# Industrial_Radio.net
KiCad netlist of a schematic drawn in Altium Designer
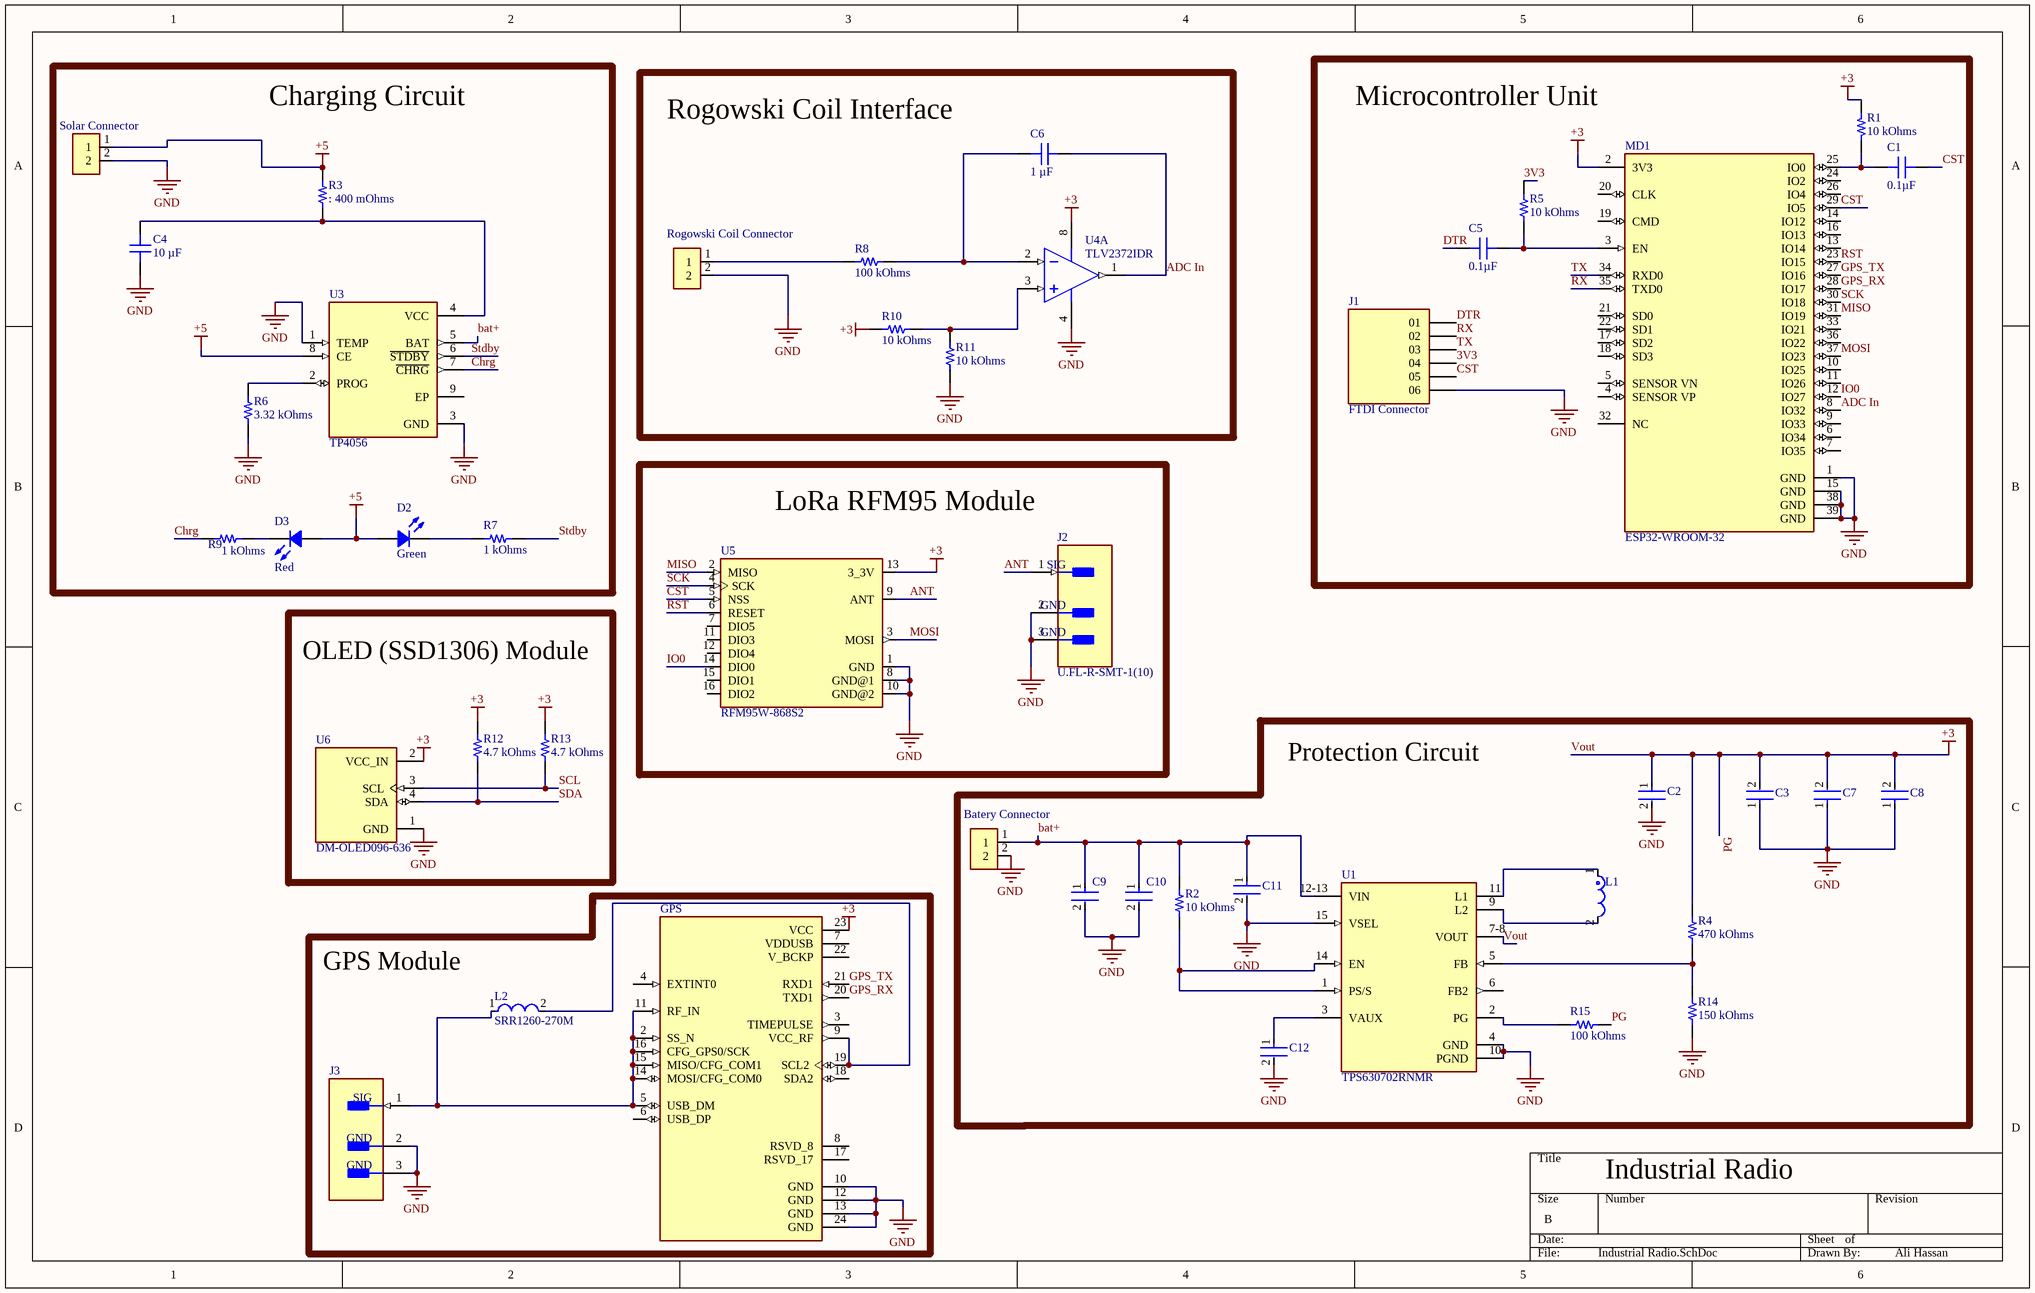
[diagram p0: Industrial Radio.SchDoc]

(export (version "E")
  (design (tool "Eeschema 10.0.6"))
  (components
    (comp (ref "Batery Connector")
      (value "B2B-PH-SM4-TB(LF)(SN)")
      (footprint "B2B-PH-SM4-TB(LF)(SN)")
      (description "Connector Header Surface Mount 2 position 0.079 (2.00mm)")
      (fields (field (name "MF") "JST Sales"))
      (libsource (lib "B2B-PH-SM4-TB_LF__SN_") (part "B2B-PH-SM4-TB(LF)(SN)"))
    )
    (comp (ref "C1")
      (value "0.1µF")
      (footprint "CAP 0603_1608")
      (description "CAP CER 0.1UF 25V X7R 0603")
      (fields
        (field (name "PART NUMBER") "06033C104K4T4A")
        (field (name "CAPACITANCE") "0.1µF")
        (field (name "MANUFACTURER") "AVX Corporation")
      )
      (libsource (lib "Celestial Altium Library - altium_library") (part "Capacitor"))
    )
    (comp (ref "C2")
      (value "TMK107BBJ106MA-T")
      (footprint "FP-0603-L_1_6_0_2-W_0_8_0-MFG")
      (description "Multilayer Ceramic Capacitor 10uF 25V X5R 20% SMD 0603 T/R")
      (fields (field (name "TOLERANCE") "20%"))
      (libsource (lib "Altium Content Vault") (part "b4654b650e69147ec39a6b967a45e02"))
    )
    (comp (ref "C3")
      (value "GRM21BC81C226ME44L")
      (footprint "FP-GRM21B-0_2-e0_2_0_7-MFG")
      (description "Chip Multilayer Ceramic Capacitors for General Purpose, 0805, 22uF, X6S, 22%, 20%, 16V")
      (fields (field (name "TOLERANCE") "20%"))
      (libsource (lib "Altium Content Vault") (part "b4654b650e69147ec39a6b967a45e02"))
    )
    (comp (ref "C4")
      (value "10 µF")
      (footprint "MURATA GRM188 0603_1608")
      (description "CAP CER 10UF 2.5V X6S 0603")
      (fields
        (field (name "PART NUMBER") "GRM188C80E106ME47D")
        (field (name "CAPACITANCE") "10 µF")
        (field (name "MANUFACTURER") "Murata Electronics")
      )
      (libsource (lib "Celestial Altium Library - altium_library") (part "Capacitor"))
    )
    (comp (ref "C5")
      (value "0.1µF")
      (footprint "CAP 0603_1608")
      (description "CAP CER 0.1UF 25V X7R 0603")
      (fields
        (field (name "PART NUMBER") "06033C104K4T4A")
        (field (name "CAPACITANCE") "0.1µF")
        (field (name "MANUFACTURER") "AVX Corporation")
      )
      (libsource (lib "Celestial Altium Library - altium_library") (part "Capacitor"))
    )
    (comp (ref "C6")
      (value "1 µF")
      (footprint "CAP 0603_1608")
      (description "CAP CER 1UF 6.3V X7R 0603")
      (fields
        (field (name "PART NUMBER") "C0603X105M9RACAUTO")
        (field (name "CAPACITANCE") "1 µF")
        (field (name "MANUFACTURER") "KEMET")
      )
      (libsource (lib "Celestial Altium Library - altium_library") (part "Capacitor"))
    )
    (comp (ref "C7")
      (value "GRM21BC81C226ME44L")
      (footprint "FP-GRM21B-0_2-e0_2_0_7-MFG")
      (description "Chip Multilayer Ceramic Capacitors for General Purpose, 0805, 22uF, X6S, 22%, 20%, 16V")
      (fields (field (name "TOLERANCE") "20%"))
      (libsource (lib "Altium Content Vault") (part "b4654b650e69147ec39a6b967a45e02"))
    )
    (comp (ref "C8")
      (value "GRM21BC81C226ME44L")
      (footprint "FP-GRM21B-0_2-e0_2_0_7-MFG")
      (description "Chip Multilayer Ceramic Capacitors for General Purpose, 0805, 22uF, X6S, 22%, 20%, 16V")
      (fields (field (name "TOLERANCE") "20%"))
      (libsource (lib "Altium Content Vault") (part "b4654b650e69147ec39a6b967a45e02"))
    )
    (comp (ref "C9")
      (value "GRM21BC71E106ME11L")
      (footprint "FP-GRM21B-0_2-e0_2_0_7-IPC_A")
      (description "Chip Multilayer Ceramic Capacitors for General Purpose, 0805, 10uF, X7S, 22%, 20%, 25V")
      (fields (field (name "TOLERANCE") "20%"))
      (libsource (lib "Altium Content Vault") (part "b4654b650e69147ec39a6b967a45e02"))
    )
    (comp (ref "C10")
      (value "GRM21BC71E106ME11L")
      (footprint "FP-GRM21B-0_2-e0_2_0_7-IPC_A")
      (description "Chip Multilayer Ceramic Capacitors for General Purpose, 0805, 10uF, X7S, 22%, 20%, 25V")
      (fields (field (name "TOLERANCE") "20%"))
      (libsource (lib "Altium Content Vault") (part "b4654b650e69147ec39a6b967a45e02"))
    )
    (comp (ref "C11")
      (value "TMK107BBJ106MA-T")
      (footprint "FP-0603-L_1_6_0_2-W_0_8_0-MFG")
      (description "Multilayer Ceramic Capacitor 10uF 25V X5R 20% SMD 0603 T/R")
      (fields (field (name "TOLERANCE") "20%"))
      (libsource (lib "Altium Content Vault") (part "b4654b650e69147ec39a6b967a45e02"))
    )
    (comp (ref "C12")
      (value "TMK105B7104MV-FR")
      (footprint "FP-0402-L_1_0_0_05-W_0_5-IPC_B")
      (description "None")
      (fields (field (name "TOLERANCE") "20%"))
      (libsource (lib "Altium Content Vault") (part "b4654b650e69147ec39a6b967a45e02"))
    )
    (comp (ref "D2")
      (value "Green")
      (footprint "LED 1206_3216 GREEN")
      (description "LED GREEN SMD")
      (fields (field (name "PART NUMBER") "HSMQ-C380") (field (name "MANUFACTURER") "Broadcom Limited"))
      (libsource (lib "Celestial Altium Library - altium_library") (part "LED"))
    )
    (comp (ref "D3")
      (value "Red")
      (footprint "LED 1206_3216 RED")
      (description "LED RED SMD")
      (fields (field (name "PART NUMBER") "HSMC-C380") (field (name "MANUFACTURER") "Broadcom Limited"))
      (libsource (lib "Celestial Altium Library - altium_library") (part "LED"))
    )
    (comp (ref "GPS")
      (value "NEO-6M-GPS")
      (footprint "XCVR_NEO-6M-GPS")
      (description "GPS Development Tools SparkFun GNSS-RTK Dead Reckoning Breakout - ZED-F9K (Qwiic)")
      (fields (field (name "MF") "u-blox"))
      (libsource (lib "NEO-6M-GPS") (part "NEO-6M-GPS"))
    )
    (comp (ref "J1")
      (value "FTDI Connector")
      (footprint "SAMTEC_MTSW-106-09-G-S-375-RA")
      (description "Connector Header Through Hole, Right Angle 6 position 0.100 (2.54mm)")
      (fields (field (name "MF") "Samtec Inc.") (field (name "MP") "MTSW-106-09-G-S-375-RA"))
      (libsource (lib "MTSW-106-09-G-S-375-RA") (part "MTSW-106-09-G-S-375-RA"))
    )
    (comp (ref "J2")
      (value "U.FL-R-SMT-1(10)")
      (footprint "FP-U_FL-R-SMT-1_10-MFG")
      (description "CONN U.FL RCPT STR 50 OHM SMD")
      (libsource (lib "Altium Content Vault") (part "7158abf7d987fa84906f6fb0d115710"))
    )
    (comp (ref "J3")
      (value "U.FL-R-SMT-1(10)")
      (footprint "FP-U_FL-R-SMT-1_10-MFG")
      (description "CONN U.FL RCPT STR 50 OHM SMD")
      (libsource (lib "") (part "7158abf7d987fa84906f6fb0d115710_1"))
    )
    (comp (ref "L1")
      (value "XFL4020-152MEC")
      (footprint "FP-XFL4020-MFG")
      (fields (field (name "TOLERANCE") "20%"))
      (libsource (lib "Altium Content Vault") (part "4cc4b267dca4c8e51f7102f422741d8"))
    )
    (comp (ref "L2")
      (value "SRR1260-270M")
      (footprint "FP-SRR1260-MFG")
      (description "FIXED IND 27UH 3.6A 45 MOHM SMD")
      (fields (field (name "TOLERANCE") "20%") (field (name "MANUFACTURER") "Bourns"))
      (libsource (lib "Altium Content Vault") (part "725321dda6339637d4d059423bc1c3c"))
    )
    (comp (ref "MD1")
      (value "ESP32-WROOM-32")
      (footprint "FP-ESP32-WROOM-32-MFG")
      (description "RX TXRX MOD WIFI SURFACE MOUNT")
      (libsource (lib "Altium Content Vault") (part "ee866abf0b6c51247b7f5cdebf2f250"))
    )
    (comp (ref "R1")
      (value "10 kOhms")
      (footprint "RES 0603_1608")
      (description "RES SMD 10K OHM 5% 1/10W 0603")
      (fields (field (name "PART NUMBER") "CRCW060310K0JNEA") (field (name "MANUFACTURER") "Vishay Dale"))
      (libsource (lib "Celestial Altium Library - altium_library") (part "Resistor"))
    )
    (comp (ref "R2")
      (value "10 kOhms")
      (footprint "RES 0603_1608")
      (description "RES 10K OHM 0.1% 1/16W 0603")
      (fields
        (field (name "PART NUMBER") "RNCS0603BKE10K0")
        (field (name "MANUFACTURER") "Stackpole Electronics Inc")
      )
      (libsource (lib "Celestial Altium Library - altium_library") (part "Resistor"))
    )
    (comp (ref "R3")
      (value "~")
      (footprint "YAGEO RES 0603_1608")
      (description "RES 0.4 OHM 1% 1/10W 0603")
      (fields
        (field (name "PART NUMBER") "RL0603FR-070R4L")
        (field (name "ALTIUM_UNNAMED_1") "400 mOhms")
        (field (name "MANUFACTURER") "Yageo")
      )
      (libsource (lib "Celestial Altium Library - altium_library") (part "Resistor"))
    )
    (comp (ref "R4")
      (value "470 kOhms")
      (footprint "YAGEO RES 0603_1608")
      (description "RES SMD 470K OHM 5% 1/10W 0603")
      (fields (field (name "PART NUMBER") "AC0603JR-07470KL") (field (name "MANUFACTURER") "Yageo"))
      (libsource (lib "Celestial Altium Library - altium_library") (part "Resistor"))
    )
    (comp (ref "R5")
      (value "10 kOhms")
      (footprint "RES 0603_1608")
      (description "RES SMD 10K OHM 5% 1/10W 0603")
      (fields (field (name "PART NUMBER") "CRCW060310K0JNEA") (field (name "MANUFACTURER") "Vishay Dale"))
      (libsource (lib "Celestial Altium Library - altium_library") (part "Resistor"))
    )
    (comp (ref "R6")
      (value "3.32 kOhms")
      (footprint "RES 0603_1608")
      (description "RES SMD 3.32K OHM 0.1% 1/5W 0603")
      (fields
        (field (name "PART NUMBER") "ERJ-PB3B3321V")
        (field (name "MANUFACTURER") "Panasonic Electronic Components")
      )
      (libsource (lib "Celestial Altium Library - altium_library") (part "Resistor"))
    )
    (comp (ref "R7")
      (value "1 kOhms")
      (footprint "RES 0603_1608")
      (description "RES SMD 1K OHM 0.1% 1/16W 0603")
      (fields
        (field (name "PART NUMBER") "CPF0603B1K0E")
        (field (name "MANUFACTURER") "TE Connectivity Passive Product")
      )
      (libsource (lib "Celestial Altium Library - altium_library") (part "Resistor"))
    )
    (comp (ref "R8")
      (value "100 kOhms")
      (footprint "RES 0603_1608")
      (description "RES 100K OHM 0.1% 1/16W 0603")
      (fields
        (field (name "PART NUMBER") "RNCS0603BKE100K")
        (field (name "MANUFACTURER") "Stackpole Electronics Inc")
      )
      (libsource (lib "Celestial Altium Library - altium_library") (part "Resistor"))
    )
    (comp (ref "R9")
      (value "1 kOhms")
      (footprint "RES 0603_1608")
      (description "RES SMD 1K OHM 0.1% 1/16W 0603")
      (fields
        (field (name "PART NUMBER") "CPF0603B1K0E")
        (field (name "MANUFACTURER") "TE Connectivity Passive Product")
      )
      (libsource (lib "Celestial Altium Library - altium_library") (part "Resistor"))
    )
    (comp (ref "R10")
      (value "10 kOhms")
      (footprint "RES 0603_1608")
      (description "RES SMD 10K OHM 5% 1/10W 0603")
      (fields (field (name "PART NUMBER") "CRCW060310K0JNEA") (field (name "MANUFACTURER") "Vishay Dale"))
      (libsource (lib "Celestial Altium Library - altium_library") (part "Resistor"))
    )
    (comp (ref "R11")
      (value "10 kOhms")
      (footprint "RES 0603_1608")
      (description "RES SMD 10K OHM 5% 1/10W 0603")
      (fields (field (name "PART NUMBER") "CRCW060310K0JNEA") (field (name "MANUFACTURER") "Vishay Dale"))
      (libsource (lib "Celestial Altium Library - altium_library") (part "Resistor"))
    )
    (comp (ref "R12")
      (value "4.7 kOhms")
      (footprint "RES 0603_1608")
      (description "RES SMD 4.7K OHM 0.1% 1/10W 0603")
      (fields
        (field (name "PART NUMBER") "ERA-3AEB472V")
        (field (name "MANUFACTURER") "Panasonic Electronic Components")
      )
      (libsource (lib "Celestial Altium Library - altium_library") (part "Resistor"))
    )
    (comp (ref "R13")
      (value "4.7 kOhms")
      (footprint "RES 0603_1608")
      (description "RES SMD 4.7K OHM 0.1% 1/10W 0603")
      (fields
        (field (name "PART NUMBER") "ERA-3AEB472V")
        (field (name "MANUFACTURER") "Panasonic Electronic Components")
      )
      (libsource (lib "Celestial Altium Library - altium_library") (part "Resistor"))
    )
    (comp (ref "R14")
      (value "150 kOhms")
      (footprint "RES 0603_1608")
      (description "RES 150K OHM 1% 1/4W 0603")
      (fields
        (field (name "PART NUMBER") "CRGP0603F150K")
        (field (name "MANUFACTURER") "TE Connectivity Passive Product")
      )
      (libsource (lib "Celestial Altium Library - altium_library") (part "Resistor"))
    )
    (comp (ref "R15")
      (value "100 kOhms")
      (footprint "RES 0603_1608")
      (description "RES 100K OHM 0.1% 1/16W 0603")
      (fields
        (field (name "PART NUMBER") "RNCS0603BKE100K")
        (field (name "MANUFACTURER") "Stackpole Electronics Inc")
      )
      (libsource (lib "Celestial Altium Library - altium_library") (part "Resistor"))
    )
    (comp (ref "Rogowski Coil Connector")
      (value "B2B-PH-SM4-TB(LF)(SN)")
      (footprint "B2B-PH-SM4-TB(LF)(SN)")
      (description "Connector Header Surface Mount 2 position 0.079 (2.00mm)")
      (fields (field (name "MF") "JST Sales"))
      (libsource (lib "B2B-PH-SM4-TB_LF__SN_") (part "B2B-PH-SM4-TB(LF)(SN)"))
    )
    (comp (ref "Solar Connector")
      (value "B2B-PH-SM4-TB(LF)(SN)")
      (footprint "B2B-PH-SM4-TB(LF)(SN)")
      (description "Connector Header Surface Mount 2 position 0.079 (2.00mm)")
      (fields (field (name "MF") "JST Sales"))
      (libsource (lib "B2B-PH-SM4-TB_LF__SN_") (part "B2B-PH-SM4-TB(LF)(SN)"))
    )
    (comp (ref "U1")
      (value "TPS630702RNMR")
      (footprint "FP-RNM0015A-MFG")
      (description "POWER MANAGEMENT")
      (libsource (lib "Altium Content Vault") (part "3b4d2662cd6691273d8b1fe1e725472"))
    )
    (comp (ref "U3")
      (value "TP4056")
      (footprint "SOP127P600X175-9N")
      (description "Complete single cell Li-Ion battery with a constant current / constant voltage linear charger")
      (fields (field (name "MF") "NanJing Top Power ASIC Corp."))
      (libsource (lib "TP4056") (part "TP4056"))
    )
    (comp (ref "U4")
      (value "TLV2372IDR")
      (footprint "D0008A_M")
      (fields (field (name "MANUFACTURER") "Texas Instruments"))
      (libsource (lib "Altium Content Vault") (part "TI-TLV_TLC-8"))
    )
    (comp (ref "U5")
      (value "RFM95W-868S2")
      (footprint "XCVR_RFM95W-868S2")
      (description "General ISM < 1GHz LoRaâ„¢ Transceiver Module 868MHz Antenna Not Included Surface Mount")
      (fields (field (name "MF") "RF"))
      (libsource (lib "RFM95W-868S2") (part "RFM95W-868S2"))
    )
    (comp (ref "U6")
      (value "DM-OLED096-636")
      (footprint "MODULE_DM-OLED096-636")
      (description "0.96â€ 128 X 64 MONOCHROME GRAPHIC OLED DISPLAY MODULE - I2C")
      (fields (field (name "MF") "Display Module"))
      (libsource (lib "DM-OLED096-636") (part "DM-OLED096-636"))
    )
  )
  (nets
    (net (code "1") (name "+3") (class "Default")
      (node (ref "C2") (pin "1") (pinfunction "1_1") (pintype "passive"))
      (node (ref "C3") (pin "2") (pinfunction "2_2") (pintype "passive"))
      (node (ref "C7") (pin "2") (pinfunction "2_2") (pintype "passive"))
      (node (ref "C8") (pin "2") (pinfunction "2_2") (pintype "passive"))
      (node (ref "GPS") (pin "23") (pinfunction "VCC_23") (pintype "power_in"))
      (node (ref "MD1") (pin "2") (pinfunction "3V3_2") (pintype "power_in"))
      (node (ref "R1") (pin "2") (pinfunction "2_2") (pintype "passive"))
      (node (ref "R10") (pin "1") (pinfunction "1_1") (pintype "passive"))
      (node (ref "R12") (pin "1") (pinfunction "1_1") (pintype "passive"))
      (node (ref "R13") (pin "1") (pinfunction "1_1") (pintype "passive"))
      (node (ref "R15") (pin "1") (pinfunction "1_1") (pintype "passive"))
      (node (ref "R4") (pin "2") (pinfunction "2_2") (pintype "passive"))
      (node (ref "U1") (pin "7-8") (pinfunction "VOUT_7-8") (pintype "passive"))
      (node (ref "U4") (pin "8") (pinfunction "VDD_8") (pintype "power_in"))
      (node (ref "U5") (pin "13") (pinfunction "3_3V_13") (pintype "power_in"))
      (node (ref "U6") (pin "2") (pinfunction "VCC_IN_2") (pintype "power_in"))
    )
    (net (code "2") (name "+5") (class "Default")
      (node (ref "D2") (pin "1") (pinfunction "1_1") (pintype "passive"))
      (node (ref "D3") (pin "1") (pinfunction "1_1") (pintype "passive"))
      (node (ref "R3") (pin "2") (pinfunction "2_2") (pintype "passive"))
      (node (ref "Solar Connector") (pin "1") (pinfunction "1_1") (pintype "bidirectional"))
      (node (ref "U3") (pin "8") (pinfunction "CE_8") (pintype "input"))
    )
    (net (code "3") (name "/3V3") (class "Default")
      (node (ref "J1") (pin "04") (pinfunction "04_04") (pintype "passive"))
      (node (ref "R5") (pin "2") (pinfunction "2_2") (pintype "passive"))
    )
    (net (code "4") (name "/ADC In") (class "Default")
      (node (ref "C6") (pin "2") (pinfunction "2_2") (pintype "passive"))
      (node (ref "MD1") (pin "8") (pinfunction "IO32_8") (pintype "bidirectional"))
      (node (ref "U4") (pin "1") (pinfunction "OUT1_1") (pintype "output"))
    )
    (net (code "5") (name "/ANT") (class "Default")
      (node (ref "J2") (pin "1") (pinfunction "SIG_1") (pintype "input"))
      (node (ref "U5") (pin "9") (pinfunction "ANT_9") (pintype "passive"))
    )
    (net (code "6") (name "/CST") (class "Default")
      (node (ref "C1") (pin "1") (pinfunction "1_1") (pintype "passive"))
      (node (ref "J1") (pin "05") (pinfunction "05_05") (pintype "passive"))
      (node (ref "MD1") (pin "29") (pinfunction "IO5_29") (pintype "bidirectional"))
      (node (ref "U5") (pin "5") (pinfunction "NSS_5") (pintype "input"))
    )
    (net (code "7") (name "/Chrg") (class "Default")
      (node (ref "R9") (pin "1") (pinfunction "1_1") (pintype "passive"))
      (node (ref "U3") (pin "7") (pinfunction "~{CHRG}_7") (pintype "output"))
    )
    (net (code "8") (name "/DTR") (class "Default")
      (node (ref "C5") (pin "1") (pinfunction "1_1") (pintype "passive"))
      (node (ref "J1") (pin "01") (pinfunction "01_01") (pintype "passive"))
    )
    (net (code "9") (name "/GPS_RX") (class "Default")
      (node (ref "GPS") (pin "20") (pinfunction "TXD1_20") (pintype "output"))
      (node (ref "MD1") (pin "28") (pinfunction "IO17_28") (pintype "bidirectional"))
    )
    (net (code "10") (name "/GPS_TX") (class "Default")
      (node (ref "GPS") (pin "21") (pinfunction "RXD1_21") (pintype "input"))
      (node (ref "MD1") (pin "27") (pinfunction "IO16_27") (pintype "bidirectional"))
    )
    (net (code "11") (name "/IO0") (class "Default")
      (node (ref "MD1") (pin "12") (pinfunction "IO27_12") (pintype "bidirectional"))
      (node (ref "U5") (pin "14") (pinfunction "DIO0_14") (pintype "bidirectional"))
    )
    (net (code "12") (name "/MISO") (class "Default")
      (node (ref "MD1") (pin "31") (pinfunction "IO19_31") (pintype "bidirectional"))
      (node (ref "U5") (pin "2") (pinfunction "MISO_2") (pintype "input"))
    )
    (net (code "13") (name "/MOSI") (class "Default")
      (node (ref "MD1") (pin "37") (pinfunction "IO23_37") (pintype "bidirectional"))
      (node (ref "U5") (pin "3") (pinfunction "MOSI_3") (pintype "output"))
    )
    (net (code "14") (name "/RST") (class "Default")
      (node (ref "MD1") (pin "23") (pinfunction "IO15_23") (pintype "bidirectional"))
      (node (ref "U5") (pin "6") (pinfunction "RESET_6") (pintype "bidirectional"))
    )
    (net (code "15") (name "/RX") (class "Default")
      (node (ref "J1") (pin "02") (pinfunction "02_02") (pintype "passive"))
      (node (ref "MD1") (pin "35") (pinfunction "TXD0_35") (pintype "bidirectional"))
    )
    (net (code "16") (name "/SCK") (class "Default")
      (node (ref "MD1") (pin "30") (pinfunction "IO18_30") (pintype "bidirectional"))
      (node (ref "U5") (pin "4") (pinfunction "SCK_4") (pintype "input"))
    )
    (net (code "17") (name "/SCL") (class "Default")
      (node (ref "R13") (pin "2") (pinfunction "2_2") (pintype "passive"))
      (node (ref "U6") (pin "3") (pinfunction "SCL_3") (pintype "input"))
    )
    (net (code "18") (name "/SDA") (class "Default")
      (node (ref "R12") (pin "2") (pinfunction "2_2") (pintype "passive"))
      (node (ref "U6") (pin "4") (pinfunction "SDA_4") (pintype "bidirectional"))
    )
    (net (code "19") (name "/Stdby") (class "Default")
      (node (ref "R7") (pin "1") (pinfunction "1_1") (pintype "passive"))
      (node (ref "U3") (pin "6") (pinfunction "~{STDBY}_6") (pintype "output"))
    )
    (net (code "20") (name "/TX") (class "Default")
      (node (ref "J1") (pin "03") (pinfunction "03_03") (pintype "passive"))
      (node (ref "MD1") (pin "34") (pinfunction "RXD0_34") (pintype "bidirectional"))
    )
    (net (code "21") (name "/bat+") (class "Default")
      (node (ref "Batery Connector") (pin "1") (pinfunction "1_1") (pintype "bidirectional"))
      (node (ref "C10") (pin "1") (pinfunction "1_1") (pintype "passive"))
      (node (ref "C11") (pin "1") (pinfunction "1_1") (pintype "passive"))
      (node (ref "C9") (pin "1") (pinfunction "1_1") (pintype "passive"))
      (node (ref "R2") (pin "2") (pinfunction "2_2") (pintype "passive"))
      (node (ref "U1") (pin "12-13") (pinfunction "VIN_12-13") (pintype "power_in"))
      (node (ref "U3") (pin "5") (pinfunction "BAT_5") (pintype "output"))
    )
    (net (code "22") (name "GND") (class "Default")
      (node (ref "Batery Connector") (pin "2") (pinfunction "2_2") (pintype "bidirectional"))
      (node (ref "C10") (pin "2") (pinfunction "2_2") (pintype "passive"))
      (node (ref "C11") (pin "2") (pinfunction "2_2") (pintype "passive"))
      (node (ref "C12") (pin "2") (pinfunction "2_2") (pintype "passive"))
      (node (ref "C2") (pin "2") (pinfunction "2_2") (pintype "passive"))
      (node (ref "C3") (pin "1") (pinfunction "1_1") (pintype "passive"))
      (node (ref "C4") (pin "1") (pinfunction "1_1") (pintype "passive"))
      (node (ref "C7") (pin "1") (pinfunction "1_1") (pintype "passive"))
      (node (ref "C8") (pin "1") (pinfunction "1_1") (pintype "passive"))
      (node (ref "C9") (pin "2") (pinfunction "2_2") (pintype "passive"))
      (node (ref "GPS") (pin "10") (pinfunction "GND_10") (pintype "power_in"))
      (node (ref "GPS") (pin "12") (pinfunction "GND_12") (pintype "power_in"))
      (node (ref "GPS") (pin "13") (pinfunction "GND_13") (pintype "power_in"))
      (node (ref "GPS") (pin "24") (pinfunction "GND_24") (pintype "power_in"))
      (node (ref "J1") (pin "06") (pinfunction "06_06") (pintype "passive"))
      (node (ref "J2") (pin "2") (pinfunction "GND_2") (pintype "power_in"))
      (node (ref "J2") (pin "3") (pinfunction "GND_3") (pintype "power_in"))
      (node (ref "J3") (pin "2") (pinfunction "GND_2") (pintype "power_in"))
      (node (ref "J3") (pin "3") (pinfunction "GND_3") (pintype "power_in"))
      (node (ref "MD1") (pin "1") (pinfunction "GND_1") (pintype "power_in"))
      (node (ref "MD1") (pin "15") (pinfunction "GND_15") (pintype "power_in"))
      (node (ref "MD1") (pin "38") (pinfunction "GND_38") (pintype "power_in"))
      (node (ref "MD1") (pin "39") (pinfunction "GND_39") (pintype "power_in"))
      (node (ref "R11") (pin "1") (pinfunction "1_1") (pintype "passive"))
      (node (ref "R14") (pin "1") (pinfunction "1_1") (pintype "passive"))
      (node (ref "R6") (pin "1") (pinfunction "1_1") (pintype "passive"))
      (node (ref "Rogowski Coil Connector") (pin "2") (pinfunction "2_2") (pintype "bidirectional"))
      (node (ref "Solar Connector") (pin "2") (pinfunction "2_2") (pintype "bidirectional"))
      (node (ref "U1") (pin "10") (pinfunction "PGND_10") (pintype "power_in"))
      (node (ref "U1") (pin "15") (pinfunction "VSEL_15") (pintype "input"))
      (node (ref "U1") (pin "4") (pinfunction "GND_4") (pintype "power_in"))
      (node (ref "U3") (pin "1") (pinfunction "TEMP_1") (pintype "input"))
      (node (ref "U3") (pin "3") (pinfunction "GND_3") (pintype "power_in"))
      (node (ref "U4") (pin "4") (pinfunction "GND_4") (pintype "power_in"))
      (node (ref "U5") (pin "1") (pinfunction "GND_1") (pintype "power_in"))
      (node (ref "U5") (pin "10") (pinfunction "GND@2_10") (pintype "power_in"))
      (node (ref "U5") (pin "8") (pinfunction "GND@1_8") (pintype "power_in"))
      (node (ref "U6") (pin "1") (pinfunction "GND_1") (pintype "power_in"))
    )
    (net (code "23") (name "Net-(D2-Pad2)") (class "Default")
      (node (ref "D2") (pin "2") (pinfunction "2_2") (pintype "passive"))
      (node (ref "R7") (pin "2") (pinfunction "2_2") (pintype "passive"))
    )
    (net (code "24") (name "Net-(D3-Pad2)") (class "Default")
      (node (ref "D3") (pin "2") (pinfunction "2_2") (pintype "passive"))
      (node (ref "R9") (pin "2") (pinfunction "2_2") (pintype "passive"))
    )
    (net (code "25") (name "Net-(GPS-CFG_GPS0{slash}SCK)") (class "Default")
      (node (ref "GPS") (pin "11") (pinfunction "RF_IN_11") (pintype "input"))
      (node (ref "GPS") (pin "14") (pinfunction "MOSI/CFG_COM0_14") (pintype "bidirectional"))
      (node (ref "GPS") (pin "15") (pinfunction "MISO/CFG_COM1_15") (pintype "input"))
      (node (ref "GPS") (pin "16") (pinfunction "CFG_GPS0/SCK_16") (pintype "input"))
      (node (ref "GPS") (pin "2") (pinfunction "SS_N_2") (pintype "input"))
      (node (ref "GPS") (pin "5") (pinfunction "USB_DM_5") (pintype "bidirectional"))
      (node (ref "J3") (pin "1") (pinfunction "SIG_1") (pintype "input"))
      (node (ref "L2") (pin "1") (pinfunction "1_1") (pintype "passive"))
    )
    (net (code "26") (name "Net-(GPS-SCL2)") (class "Default")
      (node (ref "GPS") (pin "19") (pinfunction "SCL2_19") (pintype "bidirectional"))
      (node (ref "GPS") (pin "9") (pinfunction "VCC_RF_9") (pintype "output"))
      (node (ref "L2") (pin "2") (pinfunction "2_2") (pintype "passive"))
    )
    (net (code "27") (name "Net-(MD1-EN)") (class "Default")
      (node (ref "C5") (pin "2") (pinfunction "2_2") (pintype "passive"))
      (node (ref "MD1") (pin "3") (pinfunction "EN_3") (pintype "input"))
      (node (ref "R5") (pin "1") (pinfunction "1_1") (pintype "passive"))
    )
    (net (code "28") (name "Net-(MD1-IO0)") (class "Default")
      (node (ref "C1") (pin "2") (pinfunction "2_2") (pintype "passive"))
      (node (ref "MD1") (pin "25") (pinfunction "IO0_25") (pintype "bidirectional"))
      (node (ref "R1") (pin "1") (pinfunction "1_1") (pintype "passive"))
    )
    (net (code "29") (name "Net-(R8-Pad1)") (class "Default")
      (node (ref "R8") (pin "1") (pinfunction "1_1") (pintype "passive"))
      (node (ref "Rogowski Coil Connector") (pin "1") (pinfunction "1_1") (pintype "bidirectional"))
    )
    (net (code "30") (name "Net-(U1-EN)") (class "Default")
      (node (ref "R2") (pin "1") (pinfunction "1_1") (pintype "passive"))
      (node (ref "U1") (pin "1") (pinfunction "PS/S_1") (pintype "input"))
      (node (ref "U1") (pin "14") (pinfunction "EN_14") (pintype "input"))
    )
    (net (code "31") (name "Net-(U1-FB)") (class "Default")
      (node (ref "R14") (pin "2") (pinfunction "2_2") (pintype "passive"))
      (node (ref "R4") (pin "1") (pinfunction "1_1") (pintype "passive"))
      (node (ref "U1") (pin "5") (pinfunction "FB_5") (pintype "input"))
    )
    (net (code "32") (name "Net-(U1-L1)") (class "Default")
      (node (ref "L1") (pin "1") (pinfunction "1_1") (pintype "passive"))
      (node (ref "U1") (pin "11") (pinfunction "L1_11") (pintype "passive"))
    )
    (net (code "33") (name "Net-(U1-L2)") (class "Default")
      (node (ref "L1") (pin "2") (pinfunction "2_2") (pintype "passive"))
      (node (ref "U1") (pin "9") (pinfunction "L2_9") (pintype "passive"))
    )
    (net (code "34") (name "Net-(U1-PG)") (class "Default")
      (node (ref "R15") (pin "2") (pinfunction "2_2") (pintype "passive"))
      (node (ref "U1") (pin "2") (pinfunction "PG_2") (pintype "open_collector"))
    )
    (net (code "35") (name "Net-(U1-VAUX)") (class "Default")
      (node (ref "C12") (pin "1") (pinfunction "1_1") (pintype "passive"))
      (node (ref "U1") (pin "3") (pinfunction "VAUX_3") (pintype "passive"))
    )
    (net (code "36") (name "Net-(U3-PROG)") (class "Default")
      (node (ref "R6") (pin "2") (pinfunction "2_2") (pintype "passive"))
      (node (ref "U3") (pin "2") (pinfunction "PROG_2") (pintype "bidirectional"))
    )
    (net (code "37") (name "Net-(U3-VCC)") (class "Default")
      (node (ref "C4") (pin "2") (pinfunction "2_2") (pintype "passive"))
      (node (ref "R3") (pin "1") (pinfunction "1_1") (pintype "passive"))
      (node (ref "U3") (pin "4") (pinfunction "VCC_4") (pintype "power_in"))
    )
    (net (code "38") (name "Net-(U4A-IN1+)") (class "Default")
      (node (ref "R10") (pin "2") (pinfunction "2_2") (pintype "passive"))
      (node (ref "R11") (pin "2") (pinfunction "2_2") (pintype "passive"))
      (node (ref "U4") (pin "3") (pinfunction "IN1+_3") (pintype "input"))
    )
    (net (code "39") (name "Net-(U4A-IN1-)") (class "Default")
      (node (ref "C6") (pin "1") (pinfunction "1_1") (pintype "passive"))
      (node (ref "R8") (pin "2") (pinfunction "2_2") (pintype "passive"))
      (node (ref "U4") (pin "2") (pinfunction "IN1-_2") (pintype "input"))
    )
    (net (code "40") (name "unconnected-(GPS-EXTINT0-Pad4)") (class "Default")
      (node (ref "GPS") (pin "4") (pinfunction "EXTINT0_4") (pintype "input"))
    )
    (net (code "41") (name "unconnected-(GPS-RSVD_8-Pad8)") (class "Default")
      (node (ref "GPS") (pin "8") (pinfunction "RSVD_8_8") (pintype "passive"))
    )
    (net (code "42") (name "unconnected-(GPS-RSVD_17-Pad17)") (class "Default")
      (node (ref "GPS") (pin "17") (pinfunction "RSVD_17_17") (pintype "passive"))
    )
    (net (code "43") (name "unconnected-(GPS-SDA2-Pad18)") (class "Default")
      (node (ref "GPS") (pin "18") (pinfunction "SDA2_18") (pintype "bidirectional"))
    )
    (net (code "44") (name "unconnected-(GPS-TIMEPULSE-Pad3)") (class "Default")
      (node (ref "GPS") (pin "3") (pinfunction "TIMEPULSE_3") (pintype "output"))
    )
    (net (code "45") (name "unconnected-(GPS-USB_DP-Pad6)") (class "Default")
      (node (ref "GPS") (pin "6") (pinfunction "USB_DP_6") (pintype "bidirectional"))
    )
    (net (code "46") (name "unconnected-(GPS-VDDUSB-Pad7)") (class "Default")
      (node (ref "GPS") (pin "7") (pinfunction "VDDUSB_7") (pintype "power_in"))
    )
    (net (code "47") (name "unconnected-(GPS-V_BCKP-Pad22)") (class "Default")
      (node (ref "GPS") (pin "22") (pinfunction "V_BCKP_22") (pintype "power_in"))
    )
    (net (code "48") (name "unconnected-(MD1-CLK-Pad20)") (class "Default")
      (node (ref "MD1") (pin "20") (pinfunction "CLK_20") (pintype "bidirectional"))
    )
    (net (code "49") (name "unconnected-(MD1-CMD-Pad19)") (class "Default")
      (node (ref "MD1") (pin "19") (pinfunction "CMD_19") (pintype "bidirectional"))
    )
    (net (code "50") (name "unconnected-(MD1-IO2-Pad24)") (class "Default")
      (node (ref "MD1") (pin "24") (pinfunction "IO2_24") (pintype "bidirectional"))
    )
    (net (code "51") (name "unconnected-(MD1-IO4-Pad26)") (class "Default")
      (node (ref "MD1") (pin "26") (pinfunction "IO4_26") (pintype "bidirectional"))
    )
    (net (code "52") (name "unconnected-(MD1-IO12-Pad14)") (class "Default")
      (node (ref "MD1") (pin "14") (pinfunction "IO12_14") (pintype "bidirectional"))
    )
    (net (code "53") (name "unconnected-(MD1-IO13-Pad16)") (class "Default")
      (node (ref "MD1") (pin "16") (pinfunction "IO13_16") (pintype "bidirectional"))
    )
    (net (code "54") (name "unconnected-(MD1-IO14-Pad13)") (class "Default")
      (node (ref "MD1") (pin "13") (pinfunction "IO14_13") (pintype "bidirectional"))
    )
    (net (code "55") (name "unconnected-(MD1-IO21-Pad33)") (class "Default")
      (node (ref "MD1") (pin "33") (pinfunction "IO21_33") (pintype "bidirectional"))
    )
    (net (code "56") (name "unconnected-(MD1-IO22-Pad36)") (class "Default")
      (node (ref "MD1") (pin "36") (pinfunction "IO22_36") (pintype "bidirectional"))
    )
    (net (code "57") (name "unconnected-(MD1-IO25-Pad10)") (class "Default")
      (node (ref "MD1") (pin "10") (pinfunction "IO25_10") (pintype "bidirectional"))
    )
    (net (code "58") (name "unconnected-(MD1-IO26-Pad11)") (class "Default")
      (node (ref "MD1") (pin "11") (pinfunction "IO26_11") (pintype "bidirectional"))
    )
    (net (code "59") (name "unconnected-(MD1-IO33-Pad9)") (class "Default")
      (node (ref "MD1") (pin "9") (pinfunction "IO33_9") (pintype "bidirectional"))
    )
    (net (code "60") (name "unconnected-(MD1-IO34-Pad6)") (class "Default")
      (node (ref "MD1") (pin "6") (pinfunction "IO34_6") (pintype "bidirectional"))
    )
    (net (code "61") (name "unconnected-(MD1-IO35-Pad7)") (class "Default")
      (node (ref "MD1") (pin "7") (pinfunction "IO35_7") (pintype "bidirectional"))
    )
    (net (code "62") (name "unconnected-(MD1-NC-Pad32)") (class "Default")
      (node (ref "MD1") (pin "32") (pinfunction "NC_32") (pintype "passive"))
    )
    (net (code "63") (name "unconnected-(MD1-SD0-Pad21)") (class "Default")
      (node (ref "MD1") (pin "21") (pinfunction "SD0_21") (pintype "bidirectional"))
    )
    (net (code "64") (name "unconnected-(MD1-SD1-Pad22)") (class "Default")
      (node (ref "MD1") (pin "22") (pinfunction "SD1_22") (pintype "bidirectional"))
    )
    (net (code "65") (name "unconnected-(MD1-SD2-Pad17)") (class "Default")
      (node (ref "MD1") (pin "17") (pinfunction "SD2_17") (pintype "bidirectional"))
    )
    (net (code "66") (name "unconnected-(MD1-SD3-Pad18)") (class "Default")
      (node (ref "MD1") (pin "18") (pinfunction "SD3_18") (pintype "bidirectional"))
    )
    (net (code "67") (name "unconnected-(MD1-SENSOR_VN-Pad5)") (class "Default")
      (node (ref "MD1") (pin "5") (pinfunction "SENSOR_VN_5") (pintype "bidirectional"))
    )
    (net (code "68") (name "unconnected-(MD1-SENSOR_VP-Pad4)") (class "Default")
      (node (ref "MD1") (pin "4") (pinfunction "SENSOR_VP_4") (pintype "bidirectional"))
    )
    (net (code "69") (name "unconnected-(U1-FB2-Pad6)") (class "Default")
      (node (ref "U1") (pin "6") (pinfunction "FB2_6") (pintype "output"))
    )
    (net (code "70") (name "unconnected-(U3-EP-Pad9)") (class "Default")
      (node (ref "U3") (pin "9") (pinfunction "EP_9") (pintype "passive"))
    )
    (net (code "71") (name "unconnected-(U5-DIO1-Pad15)") (class "Default")
      (node (ref "U5") (pin "15") (pinfunction "DIO1_15") (pintype "bidirectional"))
    )
    (net (code "72") (name "unconnected-(U5-DIO2-Pad16)") (class "Default")
      (node (ref "U5") (pin "16") (pinfunction "DIO2_16") (pintype "bidirectional"))
    )
    (net (code "73") (name "unconnected-(U5-DIO3-Pad11)") (class "Default")
      (node (ref "U5") (pin "11") (pinfunction "DIO3_11") (pintype "bidirectional"))
    )
    (net (code "74") (name "unconnected-(U5-DIO4-Pad12)") (class "Default")
      (node (ref "U5") (pin "12") (pinfunction "DIO4_12") (pintype "bidirectional"))
    )
    (net (code "75") (name "unconnected-(U5-DIO5-Pad7)") (class "Default")
      (node (ref "U5") (pin "7") (pinfunction "DIO5_7") (pintype "bidirectional"))
    )
  )
)
